# Esquema.net
KiCad netlist of a schematic drawn in EAGLE
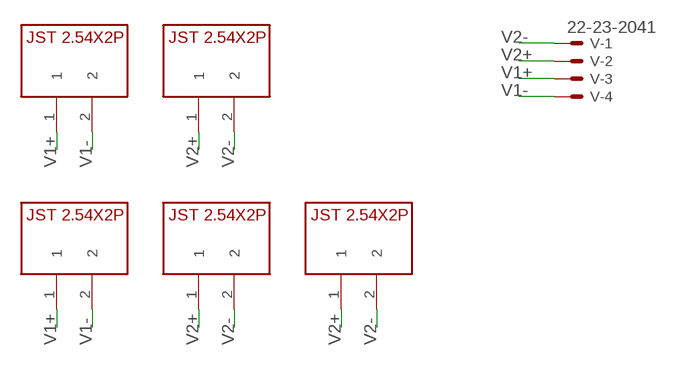
[diagram p0: schematic, sheet 1]

(export (version "E")
  (design (tool "Eeschema 10.0.6"))
  (components
    (comp (ref "U$1")
      (value "JST2.54X2P")
      (footprint "eagle-import:JST2.54X2P_FOOTPRINT")
      (libsource (lib "eagle-import") (part "JST2.54X2P"))
    )
    (comp (ref "U$2")
      (value "JST2.54X2P")
      (footprint "eagle-import:JST2.54X2P_FOOTPRINT")
      (libsource (lib "eagle-import") (part "JST2.54X2P"))
    )
    (comp (ref "U$3")
      (value "JST2.54X2P")
      (footprint "eagle-import:JST2.54X2P_FOOTPRINT")
      (libsource (lib "eagle-import") (part "JST2.54X2P"))
    )
    (comp (ref "U$4")
      (value "JST2.54X2P")
      (footprint "eagle-import:JST2.54X2P_FOOTPRINT")
      (libsource (lib "eagle-import") (part "JST2.54X2P"))
    )
    (comp (ref "U$5")
      (value "JST2.54X2P")
      (footprint "eagle-import:JST2.54X2P_FOOTPRINT")
      (libsource (lib "eagle-import") (part "JST2.54X2P"))
    )
    (comp (ref "V")
      (value "22-23-2041")
      (footprint "eagle-import:22-23-2041")
      (fields (field (name "MF") "MOLEX"))
      (libsource (lib "eagle-import") (part "22-23-2041"))
    )
  )
  (nets
    (net (code "1") (name "/V1+") (class "Default")
      (node (ref "U$1") (pin "1") (pinfunction "1_1") (pintype "bidirectional"))
      (node (ref "U$4") (pin "1") (pinfunction "1_1") (pintype "bidirectional"))
      (node (ref "V") (pin "3") (pinfunction "S_3") (pintype "passive"))
    )
    (net (code "2") (name "/V1-") (class "Default")
      (node (ref "U$1") (pin "2") (pinfunction "2_2") (pintype "bidirectional"))
      (node (ref "U$4") (pin "2") (pinfunction "2_2") (pintype "bidirectional"))
      (node (ref "V") (pin "4") (pinfunction "S_4") (pintype "passive"))
    )
    (net (code "3") (name "/V2+") (class "Default")
      (node (ref "U$2") (pin "1") (pinfunction "1_1") (pintype "bidirectional"))
      (node (ref "U$3") (pin "1") (pinfunction "1_1") (pintype "bidirectional"))
      (node (ref "U$5") (pin "1") (pinfunction "1_1") (pintype "bidirectional"))
      (node (ref "V") (pin "2") (pinfunction "S_2") (pintype "passive"))
    )
    (net (code "4") (name "/V2-") (class "Default")
      (node (ref "U$2") (pin "2") (pinfunction "2_2") (pintype "bidirectional"))
      (node (ref "U$3") (pin "2") (pinfunction "2_2") (pintype "bidirectional"))
      (node (ref "U$5") (pin "2") (pinfunction "2_2") (pintype "bidirectional"))
      (node (ref "V") (pin "1") (pinfunction "S_1") (pintype "passive"))
    )
  )
)
